# FlashAdapter_sfc.net
KiCad netlist of a schematic drawn in EAGLE
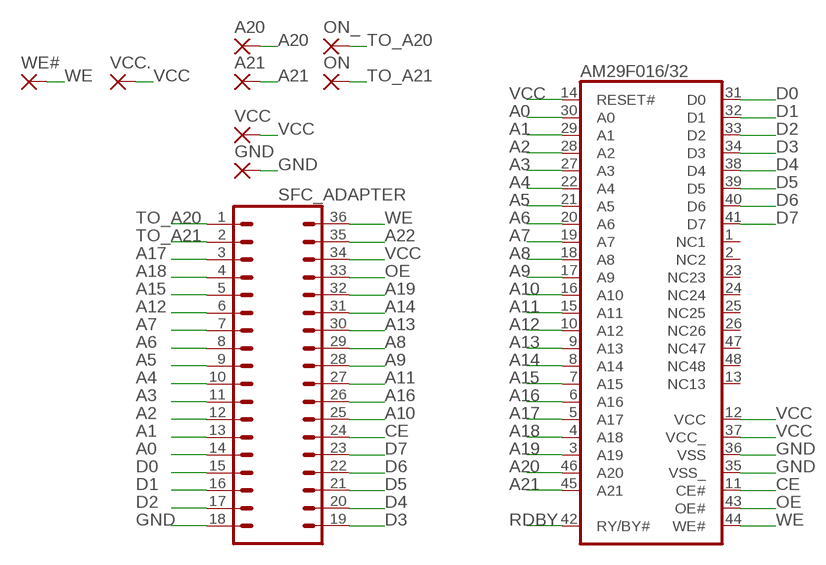
[diagram p0: schematic, sheet 1]

(export (version "E")
  (design (tool "Eeschema 10.0.6"))
  (components
    (comp (ref "A20")
      (value "SMD2")
      (footprint "eagle-import:SMD1,27-2,54")
      (libsource (lib "eagle-import") (part "SMD2"))
    )
    (comp (ref "A21")
      (value "SMD2")
      (footprint "eagle-import:SMD1,27-2,54")
      (libsource (lib "eagle-import") (part "SMD2"))
    )
    (comp (ref "AM29F016/32")
      (value "AM29F016")
      (footprint "eagle-import:TSOP48")
      (libsource (lib "eagle-import") (part "AM29F016"))
    )
    (comp (ref "GND")
      (value "SMD2")
      (footprint "eagle-import:SMD1,27-2,54")
      (libsource (lib "eagle-import") (part "SMD2"))
    )
    (comp (ref "ON")
      (value "SMD2")
      (footprint "eagle-import:SMD1,27-2,54")
      (libsource (lib "eagle-import") (part "SMD2"))
    )
    (comp (ref "ON_")
      (value "SMD2")
      (footprint "eagle-import:SMD1,27-2,54")
      (libsource (lib "eagle-import") (part "SMD2"))
    )
    (comp (ref "SFC_ADAPTER")
      (value "DIP36PTH")
      (footprint "eagle-import:DIP36")
      (libsource (lib "eagle-import") (part "DIP36PTH"))
    )
    (comp (ref "VCC")
      (value "SMD2")
      (footprint "eagle-import:SMD1,27-2,54")
      (libsource (lib "eagle-import") (part "SMD2"))
    )
    (comp (ref "VCC.")
      (value "SMD2")
      (footprint "eagle-import:SMD1,27-2,54")
      (libsource (lib "eagle-import") (part "SMD2"))
    )
    (comp (ref "WE#")
      (value "SMD2")
      (footprint "eagle-import:SMD1,27-2,54")
      (libsource (lib "eagle-import") (part "SMD2"))
    )
  )
  (nets
    (net (code "1") (name "/A0") (class "Default")
      (node (ref "AM29F016/32") (pin "30") (pinfunction "A0_30") (pintype "input"))
      (node (ref "SFC_ADAPTER") (pin "14") (pinfunction "14_14") (pintype "passive"))
    )
    (net (code "2") (name "/A1") (class "Default")
      (node (ref "AM29F016/32") (pin "29") (pinfunction "A1_29") (pintype "input"))
      (node (ref "SFC_ADAPTER") (pin "13") (pinfunction "13_13") (pintype "passive"))
    )
    (net (code "3") (name "/A2") (class "Default")
      (node (ref "AM29F016/32") (pin "28") (pinfunction "A2_28") (pintype "input"))
      (node (ref "SFC_ADAPTER") (pin "12") (pinfunction "12_12") (pintype "passive"))
    )
    (net (code "4") (name "/A3") (class "Default")
      (node (ref "AM29F016/32") (pin "27") (pinfunction "A3_27") (pintype "input"))
      (node (ref "SFC_ADAPTER") (pin "11") (pinfunction "11_11") (pintype "passive"))
    )
    (net (code "5") (name "/A4") (class "Default")
      (node (ref "AM29F016/32") (pin "22") (pinfunction "A4_22") (pintype "input"))
      (node (ref "SFC_ADAPTER") (pin "10") (pinfunction "10_10") (pintype "passive"))
    )
    (net (code "6") (name "/A5") (class "Default")
      (node (ref "AM29F016/32") (pin "21") (pinfunction "A5_21") (pintype "input"))
      (node (ref "SFC_ADAPTER") (pin "9") (pinfunction "9_9") (pintype "passive"))
    )
    (net (code "7") (name "/A6") (class "Default")
      (node (ref "AM29F016/32") (pin "20") (pinfunction "A6_20") (pintype "input"))
      (node (ref "SFC_ADAPTER") (pin "8") (pinfunction "8_8") (pintype "passive"))
    )
    (net (code "8") (name "/A7") (class "Default")
      (node (ref "AM29F016/32") (pin "19") (pinfunction "A7_19") (pintype "input"))
      (node (ref "SFC_ADAPTER") (pin "7") (pinfunction "7_7") (pintype "passive"))
    )
    (net (code "9") (name "/A8") (class "Default")
      (node (ref "AM29F016/32") (pin "18") (pinfunction "A8_18") (pintype "input"))
      (node (ref "SFC_ADAPTER") (pin "29") (pinfunction "29_29") (pintype "passive"))
    )
    (net (code "10") (name "/A9") (class "Default")
      (node (ref "AM29F016/32") (pin "17") (pinfunction "A9_17") (pintype "input"))
      (node (ref "SFC_ADAPTER") (pin "28") (pinfunction "28_28") (pintype "passive"))
    )
    (net (code "11") (name "/A10") (class "Default")
      (node (ref "AM29F016/32") (pin "16") (pinfunction "A10_16") (pintype "input"))
      (node (ref "SFC_ADAPTER") (pin "25") (pinfunction "25_25") (pintype "passive"))
    )
    (net (code "12") (name "/A11") (class "Default")
      (node (ref "AM29F016/32") (pin "15") (pinfunction "A11_15") (pintype "input"))
      (node (ref "SFC_ADAPTER") (pin "27") (pinfunction "27_27") (pintype "passive"))
    )
    (net (code "13") (name "/A12") (class "Default")
      (node (ref "AM29F016/32") (pin "10") (pinfunction "A12_10") (pintype "input"))
      (node (ref "SFC_ADAPTER") (pin "6") (pinfunction "6_6") (pintype "passive"))
    )
    (net (code "14") (name "/A13") (class "Default")
      (node (ref "AM29F016/32") (pin "9") (pinfunction "A13_9") (pintype "input"))
      (node (ref "SFC_ADAPTER") (pin "30") (pinfunction "30_30") (pintype "passive"))
    )
    (net (code "15") (name "/A14") (class "Default")
      (node (ref "AM29F016/32") (pin "8") (pinfunction "A14_8") (pintype "input"))
      (node (ref "SFC_ADAPTER") (pin "31") (pinfunction "31_31") (pintype "passive"))
    )
    (net (code "16") (name "/A15") (class "Default")
      (node (ref "AM29F016/32") (pin "7") (pinfunction "A15_7") (pintype "input"))
      (node (ref "SFC_ADAPTER") (pin "5") (pinfunction "5_5") (pintype "passive"))
    )
    (net (code "17") (name "/A16") (class "Default")
      (node (ref "AM29F016/32") (pin "6") (pinfunction "A16_6") (pintype "input"))
      (node (ref "SFC_ADAPTER") (pin "26") (pinfunction "26_26") (pintype "passive"))
    )
    (net (code "18") (name "/A17") (class "Default")
      (node (ref "AM29F016/32") (pin "5") (pinfunction "A17_5") (pintype "input"))
      (node (ref "SFC_ADAPTER") (pin "3") (pinfunction "3_3") (pintype "passive"))
    )
    (net (code "19") (name "/A18") (class "Default")
      (node (ref "AM29F016/32") (pin "4") (pinfunction "A18_4") (pintype "tri_state"))
      (node (ref "SFC_ADAPTER") (pin "4") (pinfunction "4_4") (pintype "passive"))
    )
    (net (code "20") (name "/A19") (class "Default")
      (node (ref "AM29F016/32") (pin "3") (pinfunction "A19_3") (pintype "tri_state"))
      (node (ref "SFC_ADAPTER") (pin "32") (pinfunction "32_32") (pintype "passive"))
    )
    (net (code "21") (name "/A20") (class "Default")
      (node (ref "A20") (pin "1") (pinfunction "P_1") (pintype "passive"))
      (node (ref "AM29F016/32") (pin "46") (pinfunction "A20_46") (pintype "tri_state"))
    )
    (net (code "22") (name "/A21") (class "Default")
      (node (ref "A21") (pin "1") (pinfunction "P_1") (pintype "passive"))
      (node (ref "AM29F016/32") (pin "45") (pinfunction "A21_45") (pintype "tri_state"))
    )
    (net (code "23") (name "/A22") (class "Default")
      (node (ref "SFC_ADAPTER") (pin "35") (pinfunction "35_35") (pintype "passive"))
    )
    (net (code "24") (name "/CE") (class "Default")
      (node (ref "AM29F016/32") (pin "11") (pinfunction "CE#_11") (pintype "input"))
      (node (ref "SFC_ADAPTER") (pin "24") (pinfunction "24_24") (pintype "passive"))
    )
    (net (code "25") (name "/D0") (class "Default")
      (node (ref "AM29F016/32") (pin "31") (pinfunction "D0_31") (pintype "tri_state"))
      (node (ref "SFC_ADAPTER") (pin "15") (pinfunction "15_15") (pintype "passive"))
    )
    (net (code "26") (name "/D1") (class "Default")
      (node (ref "AM29F016/32") (pin "32") (pinfunction "D1_32") (pintype "tri_state"))
      (node (ref "SFC_ADAPTER") (pin "16") (pinfunction "16_16") (pintype "passive"))
    )
    (net (code "27") (name "/D2") (class "Default")
      (node (ref "AM29F016/32") (pin "33") (pinfunction "D2_33") (pintype "tri_state"))
      (node (ref "SFC_ADAPTER") (pin "17") (pinfunction "17_17") (pintype "passive"))
    )
    (net (code "28") (name "/D3") (class "Default")
      (node (ref "AM29F016/32") (pin "34") (pinfunction "D3_34") (pintype "tri_state"))
      (node (ref "SFC_ADAPTER") (pin "19") (pinfunction "19_19") (pintype "passive"))
    )
    (net (code "29") (name "/D4") (class "Default")
      (node (ref "AM29F016/32") (pin "38") (pinfunction "D4_38") (pintype "tri_state"))
      (node (ref "SFC_ADAPTER") (pin "20") (pinfunction "20_20") (pintype "passive"))
    )
    (net (code "30") (name "/D5") (class "Default")
      (node (ref "AM29F016/32") (pin "39") (pinfunction "D5_39") (pintype "tri_state"))
      (node (ref "SFC_ADAPTER") (pin "21") (pinfunction "21_21") (pintype "passive"))
    )
    (net (code "31") (name "/D6") (class "Default")
      (node (ref "AM29F016/32") (pin "40") (pinfunction "D6_40") (pintype "tri_state"))
      (node (ref "SFC_ADAPTER") (pin "22") (pinfunction "22_22") (pintype "passive"))
    )
    (net (code "32") (name "/D7") (class "Default")
      (node (ref "AM29F016/32") (pin "41") (pinfunction "D7_41") (pintype "tri_state"))
      (node (ref "SFC_ADAPTER") (pin "23") (pinfunction "23_23") (pintype "passive"))
    )
    (net (code "33") (name "/GND") (class "Default")
      (node (ref "AM29F016/32") (pin "35") (pinfunction "VSS__35") (pintype "tri_state"))
      (node (ref "AM29F016/32") (pin "36") (pinfunction "VSS_36") (pintype "tri_state"))
      (node (ref "GND") (pin "1") (pinfunction "P_1") (pintype "passive"))
      (node (ref "SFC_ADAPTER") (pin "18") (pinfunction "18_18") (pintype "passive"))
    )
    (net (code "34") (name "/OE") (class "Default")
      (node (ref "AM29F016/32") (pin "43") (pinfunction "OE#_43") (pintype "input"))
      (node (ref "SFC_ADAPTER") (pin "33") (pinfunction "33_33") (pintype "passive"))
    )
    (net (code "35") (name "/RDBY") (class "Default")
      (node (ref "AM29F016/32") (pin "42") (pinfunction "RY/BY#_42") (pintype "output"))
    )
    (net (code "36") (name "/TO_A20") (class "Default")
      (node (ref "ON_") (pin "1") (pinfunction "P_1") (pintype "passive"))
      (node (ref "SFC_ADAPTER") (pin "1") (pinfunction "1_1") (pintype "passive"))
    )
    (net (code "37") (name "/TO_A21") (class "Default")
      (node (ref "ON") (pin "1") (pinfunction "P_1") (pintype "passive"))
      (node (ref "SFC_ADAPTER") (pin "2") (pinfunction "2_2") (pintype "passive"))
    )
    (net (code "38") (name "/VCC") (class "Default")
      (node (ref "AM29F016/32") (pin "12") (pinfunction "VCC_12") (pintype "tri_state"))
      (node (ref "AM29F016/32") (pin "14") (pinfunction "RESET#_14") (pintype "input"))
      (node (ref "AM29F016/32") (pin "37") (pinfunction "VCC__37") (pintype "tri_state"))
      (node (ref "SFC_ADAPTER") (pin "34") (pinfunction "34_34") (pintype "passive"))
      (node (ref "VCC") (pin "1") (pinfunction "P_1") (pintype "passive"))
      (node (ref "VCC.") (pin "1") (pinfunction "P_1") (pintype "passive"))
    )
    (net (code "39") (name "/WE") (class "Default")
      (node (ref "AM29F016/32") (pin "44") (pinfunction "WE#_44") (pintype "input"))
      (node (ref "SFC_ADAPTER") (pin "36") (pinfunction "36_36") (pintype "passive"))
      (node (ref "WE#") (pin "1") (pinfunction "P_1") (pintype "passive"))
    )
    (net (code "40") (name "unconnected-(AM29F016/32-NC1-Pad1)") (class "Default")
      (node (ref "AM29F016/32") (pin "1") (pinfunction "NC1_1") (pintype "tri_state"))
    )
    (net (code "41") (name "unconnected-(AM29F016/32-NC2-Pad2)") (class "Default")
      (node (ref "AM29F016/32") (pin "2") (pinfunction "NC2_2") (pintype "tri_state"))
    )
    (net (code "42") (name "unconnected-(AM29F016/32-NC13-Pad13)") (class "Default")
      (node (ref "AM29F016/32") (pin "13") (pinfunction "NC13_13") (pintype "tri_state"))
    )
    (net (code "43") (name "unconnected-(AM29F016/32-NC23-Pad23)") (class "Default")
      (node (ref "AM29F016/32") (pin "23") (pinfunction "NC23_23") (pintype "tri_state"))
    )
    (net (code "44") (name "unconnected-(AM29F016/32-NC24-Pad24)") (class "Default")
      (node (ref "AM29F016/32") (pin "24") (pinfunction "NC24_24") (pintype "tri_state"))
    )
    (net (code "45") (name "unconnected-(AM29F016/32-NC25-Pad25)") (class "Default")
      (node (ref "AM29F016/32") (pin "25") (pinfunction "NC25_25") (pintype "tri_state"))
    )
    (net (code "46") (name "unconnected-(AM29F016/32-NC26-Pad26)") (class "Default")
      (node (ref "AM29F016/32") (pin "26") (pinfunction "NC26_26") (pintype "tri_state"))
    )
    (net (code "47") (name "unconnected-(AM29F016/32-NC47-Pad47)") (class "Default")
      (node (ref "AM29F016/32") (pin "47") (pinfunction "NC47_47") (pintype "tri_state"))
    )
    (net (code "48") (name "unconnected-(AM29F016/32-NC48-Pad48)") (class "Default")
      (node (ref "AM29F016/32") (pin "48") (pinfunction "NC48_48") (pintype "tri_state"))
    )
  )
)
